# petdisk_max_dip.net
KiCad netlist of a schematic drawn in EAGLE
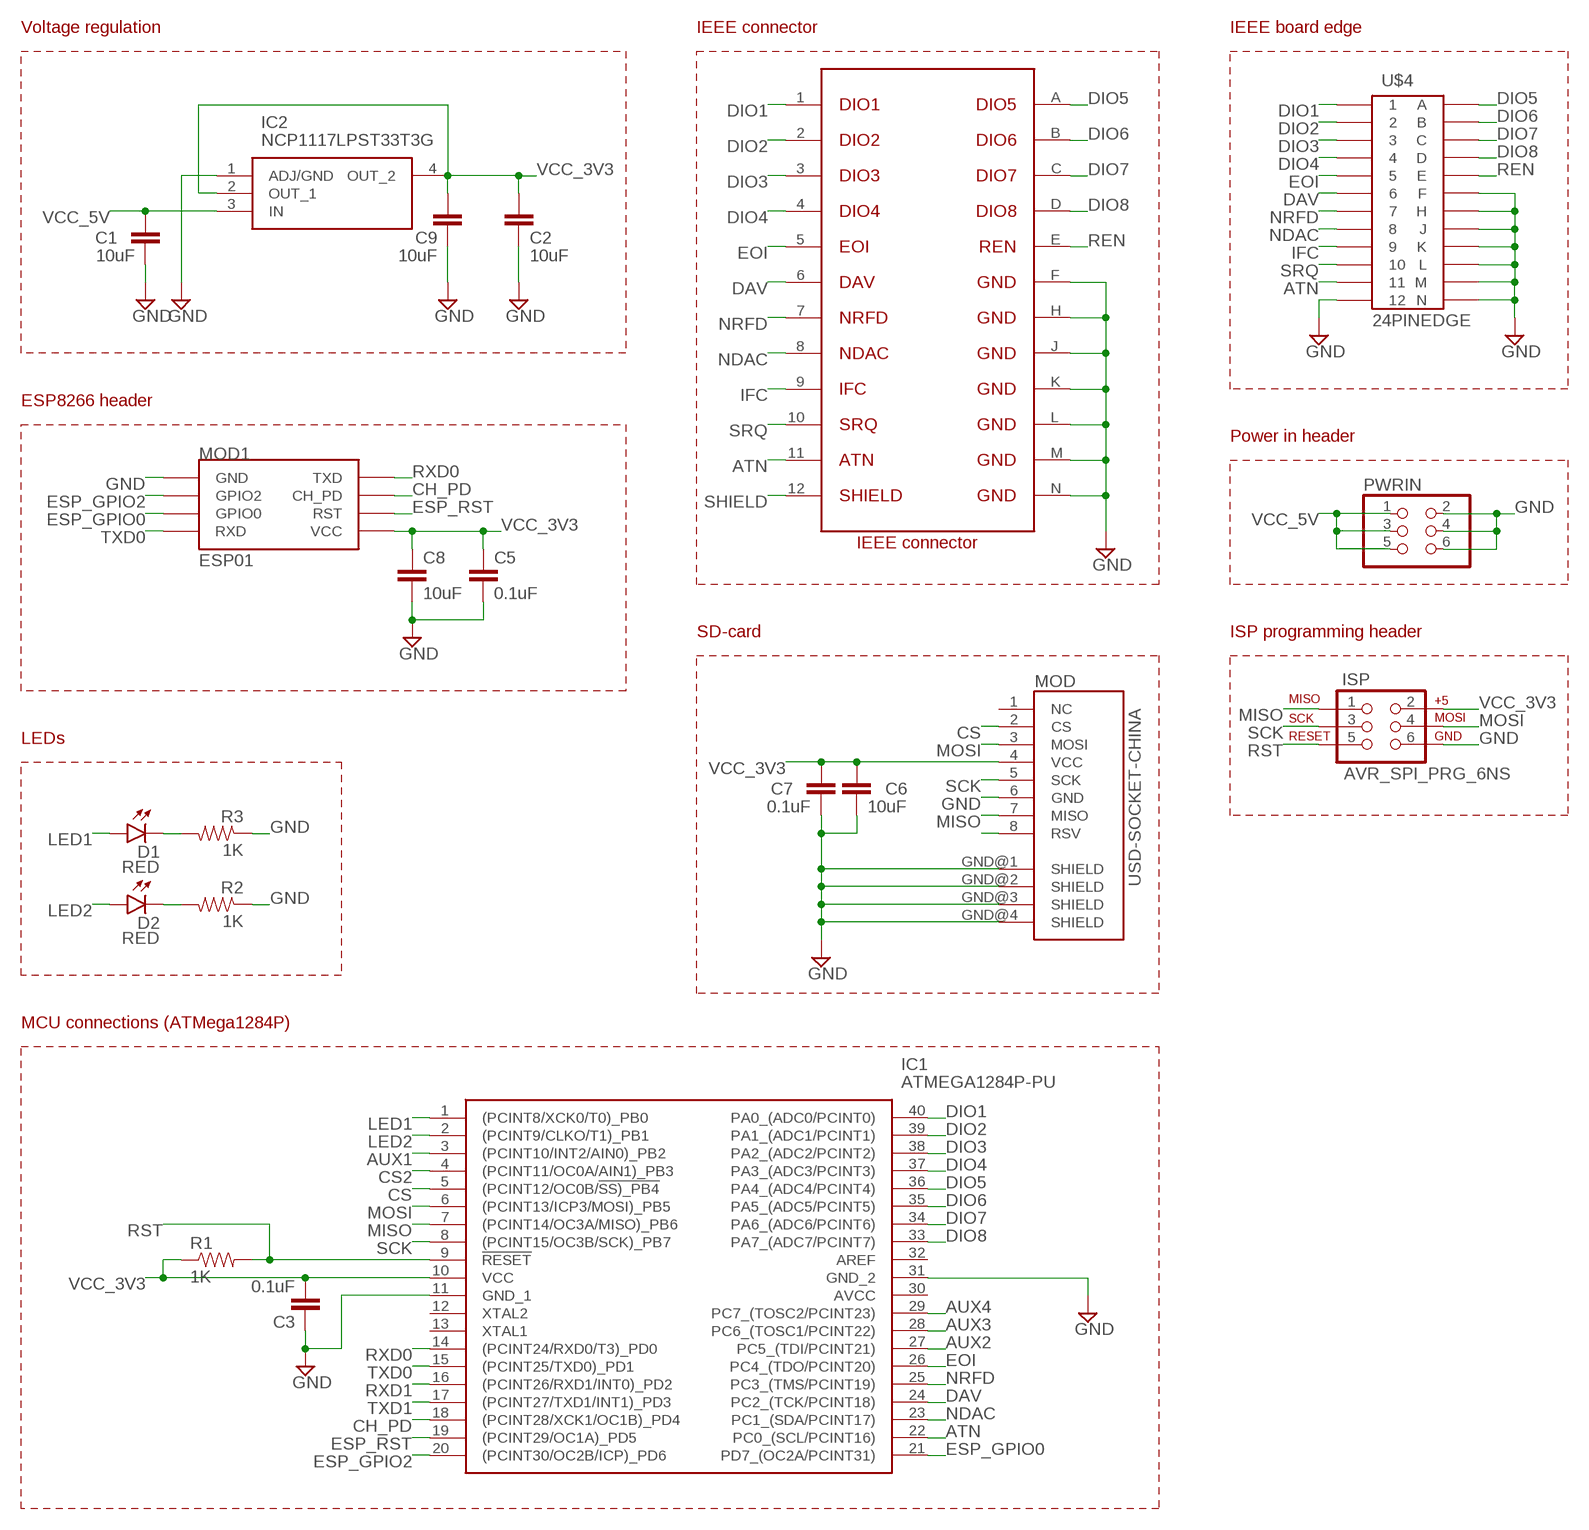
[diagram p0: schematic, sheet 1]

(export (version "E")
  (design (tool "Eeschema 10.0.6"))
  (components
    (comp (ref "C1")
      (value "10uF")
      (footprint "eagle-import:1206")
      (libsource (lib "eagle-import") (part "10UF-6.3V-20%(1206)"))
    )
    (comp (ref "C2")
      (value "10uF")
      (footprint "eagle-import:1206")
      (libsource (lib "eagle-import") (part "10UF-6.3V-20%(1206)"))
    )
    (comp (ref "C3")
      (value "0.1uF")
      (footprint "eagle-import:0603-CAP")
      (libsource (lib "eagle-import") (part "0.1UF-25V-5%(0603)"))
    )
    (comp (ref "C5")
      (value "0.1uF")
      (footprint "eagle-import:0603-CAP")
      (libsource (lib "eagle-import") (part "0.1UF-25V-5%(0603)"))
    )
    (comp (ref "C6")
      (value "10uF")
      (footprint "eagle-import:1206")
      (libsource (lib "eagle-import") (part "10UF-6.3V-20%(1206)"))
    )
    (comp (ref "C7")
      (value "0.1uF")
      (footprint "eagle-import:0603-CAP")
      (libsource (lib "eagle-import") (part "0.1UF-25V-5%(0603)"))
    )
    (comp (ref "C8")
      (value "10uF")
      (footprint "eagle-import:1206")
      (libsource (lib "eagle-import") (part "10UF-6.3V-20%(1206)"))
    )
    (comp (ref "C9")
      (value "10uF")
      (footprint "eagle-import:1206")
      (libsource (lib "eagle-import") (part "10UF-6.3V-20%(1206)"))
    )
    (comp (ref "D1")
      (value "RED")
      (footprint "eagle-import:LED-0603")
      (libsource (lib "eagle-import") (part "LED-RED0603"))
    )
    (comp (ref "D2")
      (value "RED")
      (footprint "eagle-import:LED-0603")
      (libsource (lib "eagle-import") (part "LED-RED0603"))
    )
    (comp (ref "IC1")
      (value "ATMEGA1284P-PU")
      (footprint "eagle-import:DIP1543W58P254L5175H635Q40N")
      (fields (field (name "MOUSER_PART_NUMBER") "556-ATMEGA1284P-PU"))
      (libsource (lib "eagle-import") (part "ATMEGA1284P-PU"))
    )
    (comp (ref "IC2")
      (value "NCP1117LPST33T3G")
      (footprint "eagle-import:SOT230P700X180-4N")
      (fields
        (field (name "MOUSER_PART_NUMBER") "863-NCP1117LPST33T3G")
        (field (name "RS_PART_NUMBER") "8022137P")
      )
      (libsource (lib "eagle-import") (part "NCP1117LPST33T3G"))
    )
    (comp (ref "ISP")
      (value "AVR_SPI_PRG_6NS")
      (footprint "eagle-import:2X3-NS")
      (libsource (lib "eagle-import") (part "AVR_SPI_PRG_6NS"))
    )
    (comp (ref "MOD")
      (value "USD-SOCKET-CHINA")
      (footprint "eagle-import:USD-SOCKET-PP")
      (libsource (lib "eagle-import") (part "USD-SOCKET-CHINA"))
    )
    (comp (ref "MOD1")
      (value "ESP01")
      (footprint "eagle-import:ESP01")
      (libsource (lib "eagle-import") (part "ESP01"))
    )
    (comp (ref "PWRIN")
      (value "PINHD-2X03_2.54")
      (footprint "eagle-import:2X03")
      (libsource (lib "eagle-import") (part "PINHD-2X03_2.54"))
    )
    (comp (ref "R1")
      (value "1K")
      (footprint "eagle-import:0603-RES")
      (libsource (lib "eagle-import") (part "1KOHM-1/10W-1%(0603)"))
    )
    (comp (ref "R2")
      (value "1K")
      (footprint "eagle-import:0603-RES")
      (libsource (lib "eagle-import") (part "1KOHM-1/10W-1%(0603)"))
    )
    (comp (ref "R3")
      (value "1K")
      (footprint "eagle-import:0603-RES")
      (libsource (lib "eagle-import") (part "1KOHM-1/10W-1%(0603)"))
    )
    (comp (ref "U$1")
      (value "CBM_IEEE_CONN")
      (footprint "eagle-import:UPS24CONN")
      (libsource (lib "eagle-import") (part "CBM_IEEE_CONN"))
    )
    (comp (ref "U$4")
      (value "24PINEDGE")
      (footprint "eagle-import:24PINEDGE")
      (libsource (lib "eagle-import") (part "24PINEDGE"))
    )
  )
  (nets
    (net (code "1") (name "ATN") (class "Default")
      (node (ref "IC1") (pin "22") (pinfunction "PC0_(SCL/PCINT16)_22") (pintype "bidirectional"))
      (node (ref "U$1") (pin "11") (pinfunction "11_11") (pintype "bidirectional"))
      (node (ref "U$4") (pin "11") (pinfunction "11_11") (pintype "passive"))
    )
    (net (code "2") (name "AUX1") (class "Default")
      (node (ref "IC1") (pin "3") (pinfunction "(PCINT10/INT2/AIN0)_PB2_3") (pintype "bidirectional"))
    )
    (net (code "3") (name "AUX2") (class "Default")
      (node (ref "IC1") (pin "27") (pinfunction "PC5_(TDI/PCINT21)_27") (pintype "bidirectional"))
    )
    (net (code "4") (name "AUX3") (class "Default")
      (node (ref "IC1") (pin "28") (pinfunction "PC6_(TOSC1/PCINT22)_28") (pintype "bidirectional"))
    )
    (net (code "5") (name "AUX4") (class "Default")
      (node (ref "IC1") (pin "29") (pinfunction "PC7_(TOSC2/PCINT23)_29") (pintype "bidirectional"))
    )
    (net (code "6") (name "CH_PD") (class "Default")
      (node (ref "IC1") (pin "18") (pinfunction "(PCINT28/XCK1/OC1B)_PD4_18") (pintype "bidirectional"))
      (node (ref "MOD1") (pin "CH_PD") (pinfunction "CH_PD_CH_PD") (pintype "bidirectional"))
    )
    (net (code "7") (name "CS") (class "Default")
      (node (ref "IC1") (pin "5") (pinfunction "(PCINT12/OC0B/~{SS})_PB4_5") (pintype "bidirectional"))
      (node (ref "MOD") (pin "2") (pinfunction "CS_2") (pintype "bidirectional"))
    )
    (net (code "8") (name "CS2") (class "Default")
      (node (ref "IC1") (pin "4") (pinfunction "(PCINT11/OC0A/AIN1)_PB3_4") (pintype "bidirectional"))
    )
    (net (code "9") (name "DAV") (class "Default")
      (node (ref "IC1") (pin "24") (pinfunction "PC2_(TCK/PCINT18)_24") (pintype "bidirectional"))
      (node (ref "U$1") (pin "6") (pinfunction "6_6") (pintype "bidirectional"))
      (node (ref "U$4") (pin "6") (pinfunction "6_6") (pintype "passive"))
    )
    (net (code "10") (name "DIO1") (class "Default")
      (node (ref "IC1") (pin "40") (pinfunction "PA0_(ADC0/PCINT0)_40") (pintype "bidirectional"))
      (node (ref "U$1") (pin "1") (pinfunction "1_1") (pintype "bidirectional"))
      (node (ref "U$4") (pin "1") (pinfunction "1_1") (pintype "passive"))
    )
    (net (code "11") (name "DIO2") (class "Default")
      (node (ref "IC1") (pin "39") (pinfunction "PA1_(ADC1/PCINT1)_39") (pintype "bidirectional"))
      (node (ref "U$1") (pin "2") (pinfunction "2_2") (pintype "bidirectional"))
      (node (ref "U$4") (pin "2") (pinfunction "2_2") (pintype "passive"))
    )
    (net (code "12") (name "DIO3") (class "Default")
      (node (ref "IC1") (pin "38") (pinfunction "PA2_(ADC2/PCINT2)_38") (pintype "bidirectional"))
      (node (ref "U$1") (pin "3") (pinfunction "3_3") (pintype "bidirectional"))
      (node (ref "U$4") (pin "3") (pinfunction "3_3") (pintype "passive"))
    )
    (net (code "13") (name "DIO4") (class "Default")
      (node (ref "IC1") (pin "37") (pinfunction "PA3_(ADC3/PCINT3)_37") (pintype "bidirectional"))
      (node (ref "U$1") (pin "4") (pinfunction "4_4") (pintype "bidirectional"))
      (node (ref "U$4") (pin "4") (pinfunction "4_4") (pintype "passive"))
    )
    (net (code "14") (name "DIO5") (class "Default")
      (node (ref "IC1") (pin "36") (pinfunction "PA4_(ADC4/PCINT4)_36") (pintype "bidirectional"))
      (node (ref "U$1") (pin "A") (pinfunction "A_A") (pintype "bidirectional"))
      (node (ref "U$4") (pin "A") (pinfunction "A_A") (pintype "passive"))
    )
    (net (code "15") (name "DIO6") (class "Default")
      (node (ref "IC1") (pin "35") (pinfunction "PA5_(ADC5/PCINT5)_35") (pintype "bidirectional"))
      (node (ref "U$1") (pin "B") (pinfunction "B_B") (pintype "bidirectional"))
      (node (ref "U$4") (pin "B") (pinfunction "B_B") (pintype "passive"))
    )
    (net (code "16") (name "DIO7") (class "Default")
      (node (ref "IC1") (pin "34") (pinfunction "PA6_(ADC6/PCINT6)_34") (pintype "bidirectional"))
      (node (ref "U$1") (pin "C") (pinfunction "C_C") (pintype "bidirectional"))
      (node (ref "U$4") (pin "C") (pinfunction "C_C") (pintype "passive"))
    )
    (net (code "17") (name "DIO8") (class "Default")
      (node (ref "IC1") (pin "33") (pinfunction "PA7_(ADC7/PCINT7)_33") (pintype "bidirectional"))
      (node (ref "U$1") (pin "D") (pinfunction "D_D") (pintype "bidirectional"))
      (node (ref "U$4") (pin "D") (pinfunction "D_D") (pintype "passive"))
    )
    (net (code "18") (name "EOI") (class "Default")
      (node (ref "IC1") (pin "26") (pinfunction "PC4_(TDO/PCINT20)_26") (pintype "bidirectional"))
      (node (ref "U$1") (pin "5") (pinfunction "5_5") (pintype "bidirectional"))
      (node (ref "U$4") (pin "5") (pinfunction "5_5") (pintype "passive"))
    )
    (net (code "19") (name "ESP_GPIO0") (class "Default")
      (node (ref "IC1") (pin "21") (pinfunction "PD7_(OC2A/PCINT31)_21") (pintype "bidirectional"))
      (node (ref "MOD1") (pin "GPIO0") (pinfunction "GPIO0_GPIO0") (pintype "bidirectional"))
    )
    (net (code "20") (name "ESP_GPIO2") (class "Default")
      (node (ref "IC1") (pin "20") (pinfunction "(PCINT30/OC2B/ICP)_PD6_20") (pintype "bidirectional"))
      (node (ref "MOD1") (pin "GPIO2") (pinfunction "GPIO2_GPIO2") (pintype "bidirectional"))
    )
    (net (code "21") (name "ESP_RST") (class "Default")
      (node (ref "IC1") (pin "19") (pinfunction "(PCINT29/OC1A)_PD5_19") (pintype "bidirectional"))
      (node (ref "MOD1") (pin "RST") (pinfunction "RST_RST") (pintype "bidirectional"))
    )
    (net (code "22") (name "GND") (class "Default")
      (node (ref "C1") (pin "2") (pinfunction "2_2") (pintype "passive"))
      (node (ref "C2") (pin "2") (pinfunction "2_2") (pintype "passive"))
      (node (ref "C3") (pin "1") (pinfunction "1_1") (pintype "passive"))
      (node (ref "C5") (pin "2") (pinfunction "2_2") (pintype "passive"))
      (node (ref "C6") (pin "2") (pinfunction "2_2") (pintype "passive"))
      (node (ref "C7") (pin "2") (pinfunction "2_2") (pintype "passive"))
      (node (ref "C8") (pin "2") (pinfunction "2_2") (pintype "passive"))
      (node (ref "C9") (pin "2") (pinfunction "2_2") (pintype "passive"))
      (node (ref "IC1") (pin "11") (pinfunction "GND_1_11") (pintype "bidirectional"))
      (node (ref "IC1") (pin "31") (pinfunction "GND_2_31") (pintype "bidirectional"))
      (node (ref "IC2") (pin "1") (pinfunction "ADJ/GND_1") (pintype "power_in"))
      (node (ref "ISP") (pin "6") (pinfunction "6_6") (pintype "passive"))
      (node (ref "MOD") (pin "6") (pinfunction "GND_6") (pintype "bidirectional"))
      (node (ref "MOD") (pin "GND@1") (pinfunction "SHIELD_GND@1") (pintype "bidirectional"))
      (node (ref "MOD") (pin "GND@2") (pinfunction "SHIELD_GND@2") (pintype "bidirectional"))
      (node (ref "MOD") (pin "GND@3") (pinfunction "SHIELD_GND@3") (pintype "bidirectional"))
      (node (ref "MOD") (pin "GND@4") (pinfunction "SHIELD_GND@4") (pintype "bidirectional"))
      (node (ref "MOD1") (pin "GND") (pinfunction "GND_GND") (pintype "bidirectional"))
      (node (ref "PWRIN") (pin "2") (pinfunction "2_2") (pintype "passive"))
      (node (ref "PWRIN") (pin "4") (pinfunction "4_4") (pintype "passive"))
      (node (ref "PWRIN") (pin "6") (pinfunction "6_6") (pintype "passive"))
      (node (ref "R2") (pin "1") (pinfunction "1_1") (pintype "passive"))
      (node (ref "R3") (pin "1") (pinfunction "1_1") (pintype "passive"))
      (node (ref "U$1") (pin "F") (pinfunction "F_F") (pintype "bidirectional"))
      (node (ref "U$1") (pin "H") (pinfunction "H_H") (pintype "bidirectional"))
      (node (ref "U$1") (pin "J") (pinfunction "J_J") (pintype "bidirectional"))
      (node (ref "U$1") (pin "K") (pinfunction "K_K") (pintype "bidirectional"))
      (node (ref "U$1") (pin "L") (pinfunction "L_L") (pintype "bidirectional"))
      (node (ref "U$1") (pin "M") (pinfunction "M_M") (pintype "bidirectional"))
      (node (ref "U$1") (pin "N") (pinfunction "N_N") (pintype "bidirectional"))
      (node (ref "U$4") (pin "12") (pinfunction "12_12") (pintype "passive"))
      (node (ref "U$4") (pin "F") (pinfunction "F_F") (pintype "passive"))
      (node (ref "U$4") (pin "H") (pinfunction "H_H") (pintype "passive"))
      (node (ref "U$4") (pin "J") (pinfunction "J_J") (pintype "passive"))
      (node (ref "U$4") (pin "K") (pinfunction "K_K") (pintype "passive"))
      (node (ref "U$4") (pin "L") (pinfunction "L_L") (pintype "passive"))
      (node (ref "U$4") (pin "M") (pinfunction "M_M") (pintype "passive"))
      (node (ref "U$4") (pin "N") (pinfunction "N_N") (pintype "passive"))
    )
    (net (code "23") (name "IFC") (class "Default")
      (node (ref "U$1") (pin "9") (pinfunction "9_9") (pintype "bidirectional"))
      (node (ref "U$4") (pin "9") (pinfunction "9_9") (pintype "passive"))
    )
    (net (code "24") (name "LED1") (class "Default")
      (node (ref "D1") (pin "A") (pinfunction "A_A") (pintype "passive"))
      (node (ref "IC1") (pin "1") (pinfunction "(PCINT8/XCK0/T0)_PB0_1") (pintype "bidirectional"))
    )
    (net (code "25") (name "LED2") (class "Default")
      (node (ref "D2") (pin "A") (pinfunction "A_A") (pintype "passive"))
      (node (ref "IC1") (pin "2") (pinfunction "(PCINT9/CLKO/T1)_PB1_2") (pintype "bidirectional"))
    )
    (net (code "26") (name "MISO") (class "Default")
      (node (ref "IC1") (pin "7") (pinfunction "(PCINT14/OC3A/MISO)_PB6_7") (pintype "bidirectional"))
      (node (ref "ISP") (pin "1") (pinfunction "1_1") (pintype "passive"))
      (node (ref "MOD") (pin "7") (pinfunction "MISO_7") (pintype "bidirectional"))
    )
    (net (code "27") (name "MOSI") (class "Default")
      (node (ref "IC1") (pin "6") (pinfunction "(PCINT13/ICP3/MOSI)_PB5_6") (pintype "bidirectional"))
      (node (ref "ISP") (pin "4") (pinfunction "4_4") (pintype "passive"))
      (node (ref "MOD") (pin "3") (pinfunction "MOSI_3") (pintype "bidirectional"))
    )
    (net (code "28") (name "NDAC") (class "Default")
      (node (ref "IC1") (pin "23") (pinfunction "PC1_(SDA/PCINT17)_23") (pintype "bidirectional"))
      (node (ref "U$1") (pin "8") (pinfunction "8_8") (pintype "bidirectional"))
      (node (ref "U$4") (pin "8") (pinfunction "8_8") (pintype "passive"))
    )
    (net (code "29") (name "NRFD") (class "Default")
      (node (ref "IC1") (pin "25") (pinfunction "PC3_(TMS/PCINT19)_25") (pintype "bidirectional"))
      (node (ref "U$1") (pin "7") (pinfunction "7_7") (pintype "bidirectional"))
      (node (ref "U$4") (pin "7") (pinfunction "7_7") (pintype "passive"))
    )
    (net (code "30") (name "Net-(D1-PadC)") (class "Default")
      (node (ref "D1") (pin "C") (pinfunction "C_C") (pintype "passive"))
      (node (ref "R3") (pin "2") (pinfunction "2_2") (pintype "passive"))
    )
    (net (code "31") (name "Net-(D2-PadC)") (class "Default")
      (node (ref "D2") (pin "C") (pinfunction "C_C") (pintype "passive"))
      (node (ref "R2") (pin "2") (pinfunction "2_2") (pintype "passive"))
    )
    (net (code "32") (name "REN") (class "Default")
      (node (ref "U$1") (pin "E") (pinfunction "E_E") (pintype "bidirectional"))
      (node (ref "U$4") (pin "E") (pinfunction "E_E") (pintype "passive"))
    )
    (net (code "33") (name "RST") (class "Default")
      (node (ref "IC1") (pin "9") (pinfunction "~{RESET}_9") (pintype "bidirectional"))
      (node (ref "ISP") (pin "5") (pinfunction "5_5") (pintype "passive"))
      (node (ref "R1") (pin "2") (pinfunction "2_2") (pintype "passive"))
    )
    (net (code "34") (name "RXD0") (class "Default")
      (node (ref "IC1") (pin "14") (pinfunction "(PCINT24/RXD0/T3)_PD0_14") (pintype "bidirectional"))
      (node (ref "MOD1") (pin "TX") (pinfunction "TXD_TX") (pintype "bidirectional"))
    )
    (net (code "35") (name "RXD1") (class "Default")
      (node (ref "IC1") (pin "16") (pinfunction "(PCINT26/RXD1/INT0)_PD2_16") (pintype "bidirectional"))
    )
    (net (code "36") (name "SCK") (class "Default")
      (node (ref "IC1") (pin "8") (pinfunction "(PCINT15/OC3B/SCK)_PB7_8") (pintype "bidirectional"))
      (node (ref "ISP") (pin "3") (pinfunction "3_3") (pintype "passive"))
      (node (ref "MOD") (pin "5") (pinfunction "SCK_5") (pintype "bidirectional"))
    )
    (net (code "37") (name "SHIELD") (class "Default")
      (node (ref "U$1") (pin "12") (pinfunction "12_12") (pintype "bidirectional"))
    )
    (net (code "38") (name "SRQ") (class "Default")
      (node (ref "U$1") (pin "10") (pinfunction "10_10") (pintype "bidirectional"))
      (node (ref "U$4") (pin "10") (pinfunction "10_10") (pintype "passive"))
    )
    (net (code "39") (name "TXD0") (class "Default")
      (node (ref "IC1") (pin "15") (pinfunction "(PCINT25/TXD0)_PD1_15") (pintype "bidirectional"))
      (node (ref "MOD1") (pin "RX") (pinfunction "RXD_RX") (pintype "bidirectional"))
    )
    (net (code "40") (name "TXD1") (class "Default")
      (node (ref "IC1") (pin "17") (pinfunction "(PCINT27/TXD1/INT1)_PD3_17") (pintype "bidirectional"))
    )
    (net (code "41") (name "VCC_3V3") (class "Default")
      (node (ref "C2") (pin "1") (pinfunction "1_1") (pintype "passive"))
      (node (ref "C3") (pin "2") (pinfunction "2_2") (pintype "passive"))
      (node (ref "C5") (pin "1") (pinfunction "1_1") (pintype "passive"))
      (node (ref "C6") (pin "1") (pinfunction "1_1") (pintype "passive"))
      (node (ref "C7") (pin "1") (pinfunction "1_1") (pintype "passive"))
      (node (ref "C8") (pin "1") (pinfunction "1_1") (pintype "passive"))
      (node (ref "C9") (pin "1") (pinfunction "1_1") (pintype "passive"))
      (node (ref "IC1") (pin "10") (pinfunction "VCC_10") (pintype "bidirectional"))
      (node (ref "IC2") (pin "2") (pinfunction "OUT_1_2") (pintype "output"))
      (node (ref "IC2") (pin "4") (pinfunction "OUT_2_4") (pintype "output"))
      (node (ref "ISP") (pin "2") (pinfunction "2_2") (pintype "passive"))
      (node (ref "MOD") (pin "4") (pinfunction "VCC_4") (pintype "bidirectional"))
      (node (ref "MOD1") (pin "VCC") (pinfunction "VCC_VCC") (pintype "bidirectional"))
      (node (ref "R1") (pin "1") (pinfunction "1_1") (pintype "passive"))
    )
    (net (code "42") (name "VCC_5V") (class "Default")
      (node (ref "C1") (pin "1") (pinfunction "1_1") (pintype "passive"))
      (node (ref "IC2") (pin "3") (pinfunction "IN_3") (pintype "input"))
      (node (ref "PWRIN") (pin "1") (pinfunction "1_1") (pintype "passive"))
      (node (ref "PWRIN") (pin "3") (pinfunction "3_3") (pintype "passive"))
      (node (ref "PWRIN") (pin "5") (pinfunction "5_5") (pintype "passive"))
    )
    (net (code "43") (name "unconnected-(IC1-AREF-Pad32)") (class "Default")
      (node (ref "IC1") (pin "32") (pinfunction "AREF_32") (pintype "bidirectional"))
    )
    (net (code "44") (name "unconnected-(IC1-AVCC-Pad30)") (class "Default")
      (node (ref "IC1") (pin "30") (pinfunction "AVCC_30") (pintype "bidirectional"))
    )
    (net (code "45") (name "unconnected-(IC1-XTAL1-Pad13)") (class "Default")
      (node (ref "IC1") (pin "13") (pinfunction "XTAL1_13") (pintype "bidirectional"))
    )
    (net (code "46") (name "unconnected-(IC1-XTAL2-Pad12)") (class "Default")
      (node (ref "IC1") (pin "12") (pinfunction "XTAL2_12") (pintype "bidirectional"))
    )
    (net (code "47") (name "unconnected-(MOD-NC-Pad1)") (class "Default")
      (node (ref "MOD") (pin "1") (pinfunction "NC_1") (pintype "bidirectional"))
    )
    (net (code "48") (name "unconnected-(MOD-RSV-Pad8)") (class "Default")
      (node (ref "MOD") (pin "8") (pinfunction "RSV_8") (pintype "bidirectional"))
    )
  )
)
